# rj45External.net
KiCad netlist of a schematic drawn in EAGLE
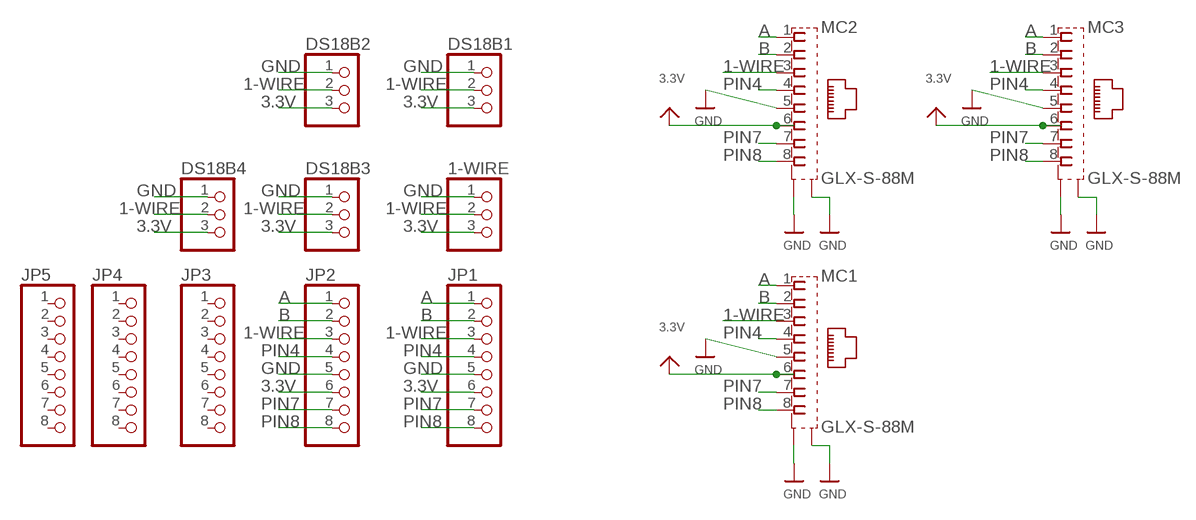
[diagram p0: schematic, sheet 1]

(export (version "E")
  (design (tool "Eeschema 10.0.6"))
  (components
    (comp (ref "1-WIRE")
      (value "PINHD-1X3")
      (footprint "eagle-import:1X03")
      (libsource (lib "eagle-import") (part "PINHD-1X3"))
    )
    (comp (ref "DS18B1")
      (value "PINHD-1X3")
      (footprint "eagle-import:1X03")
      (libsource (lib "eagle-import") (part "PINHD-1X3"))
    )
    (comp (ref "DS18B2")
      (value "PINHD-1X3")
      (footprint "eagle-import:1X03")
      (libsource (lib "eagle-import") (part "PINHD-1X3"))
    )
    (comp (ref "DS18B3")
      (value "PINHD-1X3")
      (footprint "eagle-import:1X03")
      (libsource (lib "eagle-import") (part "PINHD-1X3"))
    )
    (comp (ref "DS18B4")
      (value "PINHD-1X3")
      (footprint "eagle-import:1X03")
      (libsource (lib "eagle-import") (part "PINHD-1X3"))
    )
    (comp (ref "JP1")
      (value "PINHD-1X8BIG")
      (footprint "eagle-import:1X08-BIG")
      (libsource (lib "eagle-import") (part "PINHD-1X8BIG"))
    )
    (comp (ref "JP2")
      (value "PINHD-1X8BIG")
      (footprint "eagle-import:1X08-BIG")
      (libsource (lib "eagle-import") (part "PINHD-1X8BIG"))
    )
    (comp (ref "JP3")
      (value "PINHD-1X8BIG")
      (footprint "eagle-import:1X08-BIG")
      (libsource (lib "eagle-import") (part "PINHD-1X8BIG"))
    )
    (comp (ref "JP4")
      (value "PINHD-1X8BIG")
      (footprint "eagle-import:1X08-BIG")
      (libsource (lib "eagle-import") (part "PINHD-1X8BIG"))
    )
    (comp (ref "JP5")
      (value "PINHD-1X8BIG")
      (footprint "eagle-import:1X08-BIG")
      (libsource (lib "eagle-import") (part "PINHD-1X8BIG"))
    )
    (comp (ref "MC1")
      (value "GLX-S-88M")
      (footprint "eagle-import:GLX-S-88M")
      (libsource (lib "eagle-import") (part "GLX-S-88M"))
    )
    (comp (ref "MC2")
      (value "GLX-S-88M")
      (footprint "eagle-import:GLX-S-88M")
      (libsource (lib "eagle-import") (part "GLX-S-88M"))
    )
    (comp (ref "MC3")
      (value "GLX-S-88M")
      (footprint "eagle-import:GLX-S-88M")
      (libsource (lib "eagle-import") (part "GLX-S-88M"))
    )
  )
  (nets
    (net (code "1") (name "/1-WIRE") (class "Default")
      (node (ref "1-WIRE") (pin "2") (pinfunction "2_2") (pintype "passive"))
      (node (ref "DS18B1") (pin "2") (pinfunction "2_2") (pintype "passive"))
      (node (ref "DS18B2") (pin "2") (pinfunction "2_2") (pintype "passive"))
      (node (ref "DS18B3") (pin "2") (pinfunction "2_2") (pintype "passive"))
      (node (ref "DS18B4") (pin "2") (pinfunction "2_2") (pintype "passive"))
      (node (ref "JP1") (pin "3") (pinfunction "3_3") (pintype "passive"))
      (node (ref "JP2") (pin "3") (pinfunction "3_3") (pintype "passive"))
      (node (ref "MC1") (pin "3") (pinfunction "3_3") (pintype "passive"))
      (node (ref "MC2") (pin "3") (pinfunction "3_3") (pintype "passive"))
      (node (ref "MC3") (pin "3") (pinfunction "3_3") (pintype "passive"))
    )
    (net (code "2") (name "/A") (class "Default")
      (node (ref "JP1") (pin "1") (pinfunction "1_1") (pintype "passive"))
      (node (ref "JP2") (pin "1") (pinfunction "1_1") (pintype "passive"))
      (node (ref "MC1") (pin "1") (pinfunction "1_1") (pintype "passive"))
      (node (ref "MC2") (pin "1") (pinfunction "1_1") (pintype "passive"))
      (node (ref "MC3") (pin "1") (pinfunction "1_1") (pintype "passive"))
    )
    (net (code "3") (name "/B") (class "Default")
      (node (ref "JP1") (pin "2") (pinfunction "2_2") (pintype "passive"))
      (node (ref "JP2") (pin "2") (pinfunction "2_2") (pintype "passive"))
      (node (ref "MC1") (pin "2") (pinfunction "2_2") (pintype "passive"))
      (node (ref "MC2") (pin "2") (pinfunction "2_2") (pintype "passive"))
      (node (ref "MC3") (pin "2") (pinfunction "2_2") (pintype "passive"))
    )
    (net (code "4") (name "/PIN4") (class "Default")
      (node (ref "JP1") (pin "4") (pinfunction "4_4") (pintype "passive"))
      (node (ref "JP2") (pin "4") (pinfunction "4_4") (pintype "passive"))
      (node (ref "MC1") (pin "4") (pinfunction "4_4") (pintype "passive"))
      (node (ref "MC2") (pin "4") (pinfunction "4_4") (pintype "passive"))
      (node (ref "MC3") (pin "4") (pinfunction "4_4") (pintype "passive"))
    )
    (net (code "5") (name "/PIN7") (class "Default")
      (node (ref "JP1") (pin "7") (pinfunction "7_7") (pintype "passive"))
      (node (ref "JP2") (pin "7") (pinfunction "7_7") (pintype "passive"))
      (node (ref "MC1") (pin "7") (pinfunction "7_7") (pintype "passive"))
      (node (ref "MC2") (pin "7") (pinfunction "7_7") (pintype "passive"))
      (node (ref "MC3") (pin "7") (pinfunction "7_7") (pintype "passive"))
    )
    (net (code "6") (name "/PIN8") (class "Default")
      (node (ref "JP1") (pin "8") (pinfunction "8_8") (pintype "passive"))
      (node (ref "JP2") (pin "8") (pinfunction "8_8") (pintype "passive"))
      (node (ref "MC1") (pin "8") (pinfunction "8_8") (pintype "passive"))
      (node (ref "MC2") (pin "8") (pinfunction "8_8") (pintype "passive"))
      (node (ref "MC3") (pin "8") (pinfunction "8_8") (pintype "passive"))
    )
    (net (code "7") (name "3.3V") (class "Default")
      (node (ref "1-WIRE") (pin "3") (pinfunction "3_3") (pintype "passive"))
      (node (ref "DS18B1") (pin "3") (pinfunction "3_3") (pintype "passive"))
      (node (ref "DS18B2") (pin "3") (pinfunction "3_3") (pintype "passive"))
      (node (ref "DS18B3") (pin "3") (pinfunction "3_3") (pintype "passive"))
      (node (ref "DS18B4") (pin "3") (pinfunction "3_3") (pintype "passive"))
      (node (ref "JP1") (pin "6") (pinfunction "6_6") (pintype "passive"))
      (node (ref "JP2") (pin "6") (pinfunction "6_6") (pintype "passive"))
      (node (ref "MC1") (pin "6") (pinfunction "6_6") (pintype "passive"))
      (node (ref "MC2") (pin "6") (pinfunction "6_6") (pintype "passive"))
      (node (ref "MC3") (pin "6") (pinfunction "6_6") (pintype "passive"))
    )
    (net (code "8") (name "GND") (class "Default")
      (node (ref "1-WIRE") (pin "1") (pinfunction "1_1") (pintype "passive"))
      (node (ref "DS18B1") (pin "1") (pinfunction "1_1") (pintype "passive"))
      (node (ref "DS18B2") (pin "1") (pinfunction "1_1") (pintype "passive"))
      (node (ref "DS18B3") (pin "1") (pinfunction "1_1") (pintype "passive"))
      (node (ref "DS18B4") (pin "1") (pinfunction "1_1") (pintype "passive"))
      (node (ref "JP1") (pin "5") (pinfunction "5_5") (pintype "passive"))
      (node (ref "JP2") (pin "5") (pinfunction "5_5") (pintype "passive"))
      (node (ref "MC1") (pin "5") (pinfunction "5_5") (pintype "passive"))
      (node (ref "MC1") (pin "S1") (pinfunction "S1_S1") (pintype "passive"))
      (node (ref "MC1") (pin "S2") (pinfunction "S2_S2") (pintype "passive"))
      (node (ref "MC2") (pin "5") (pinfunction "5_5") (pintype "passive"))
      (node (ref "MC2") (pin "S1") (pinfunction "S1_S1") (pintype "passive"))
      (node (ref "MC2") (pin "S2") (pinfunction "S2_S2") (pintype "passive"))
      (node (ref "MC3") (pin "5") (pinfunction "5_5") (pintype "passive"))
      (node (ref "MC3") (pin "S1") (pinfunction "S1_S1") (pintype "passive"))
      (node (ref "MC3") (pin "S2") (pinfunction "S2_S2") (pintype "passive"))
    )
    (net (code "9") (name "unconnected-(JP3-Pad1)") (class "Default")
      (node (ref "JP3") (pin "1") (pinfunction "1_1") (pintype "passive"))
    )
    (net (code "10") (name "unconnected-(JP3-Pad2)") (class "Default")
      (node (ref "JP3") (pin "2") (pinfunction "2_2") (pintype "passive"))
    )
    (net (code "11") (name "unconnected-(JP3-Pad3)") (class "Default")
      (node (ref "JP3") (pin "3") (pinfunction "3_3") (pintype "passive"))
    )
    (net (code "12") (name "unconnected-(JP3-Pad4)") (class "Default")
      (node (ref "JP3") (pin "4") (pinfunction "4_4") (pintype "passive"))
    )
    (net (code "13") (name "unconnected-(JP3-Pad5)") (class "Default")
      (node (ref "JP3") (pin "5") (pinfunction "5_5") (pintype "passive"))
    )
    (net (code "14") (name "unconnected-(JP3-Pad6)") (class "Default")
      (node (ref "JP3") (pin "6") (pinfunction "6_6") (pintype "passive"))
    )
    (net (code "15") (name "unconnected-(JP3-Pad7)") (class "Default")
      (node (ref "JP3") (pin "7") (pinfunction "7_7") (pintype "passive"))
    )
    (net (code "16") (name "unconnected-(JP3-Pad8)") (class "Default")
      (node (ref "JP3") (pin "8") (pinfunction "8_8") (pintype "passive"))
    )
    (net (code "17") (name "unconnected-(JP4-Pad1)") (class "Default")
      (node (ref "JP4") (pin "1") (pinfunction "1_1") (pintype "passive"))
    )
    (net (code "18") (name "unconnected-(JP4-Pad2)") (class "Default")
      (node (ref "JP4") (pin "2") (pinfunction "2_2") (pintype "passive"))
    )
    (net (code "19") (name "unconnected-(JP4-Pad3)") (class "Default")
      (node (ref "JP4") (pin "3") (pinfunction "3_3") (pintype "passive"))
    )
    (net (code "20") (name "unconnected-(JP4-Pad4)") (class "Default")
      (node (ref "JP4") (pin "4") (pinfunction "4_4") (pintype "passive"))
    )
    (net (code "21") (name "unconnected-(JP4-Pad5)") (class "Default")
      (node (ref "JP4") (pin "5") (pinfunction "5_5") (pintype "passive"))
    )
    (net (code "22") (name "unconnected-(JP4-Pad6)") (class "Default")
      (node (ref "JP4") (pin "6") (pinfunction "6_6") (pintype "passive"))
    )
    (net (code "23") (name "unconnected-(JP4-Pad7)") (class "Default")
      (node (ref "JP4") (pin "7") (pinfunction "7_7") (pintype "passive"))
    )
    (net (code "24") (name "unconnected-(JP4-Pad8)") (class "Default")
      (node (ref "JP4") (pin "8") (pinfunction "8_8") (pintype "passive"))
    )
    (net (code "25") (name "unconnected-(JP5-Pad1)") (class "Default")
      (node (ref "JP5") (pin "1") (pinfunction "1_1") (pintype "passive"))
    )
    (net (code "26") (name "unconnected-(JP5-Pad2)") (class "Default")
      (node (ref "JP5") (pin "2") (pinfunction "2_2") (pintype "passive"))
    )
    (net (code "27") (name "unconnected-(JP5-Pad3)") (class "Default")
      (node (ref "JP5") (pin "3") (pinfunction "3_3") (pintype "passive"))
    )
    (net (code "28") (name "unconnected-(JP5-Pad4)") (class "Default")
      (node (ref "JP5") (pin "4") (pinfunction "4_4") (pintype "passive"))
    )
    (net (code "29") (name "unconnected-(JP5-Pad5)") (class "Default")
      (node (ref "JP5") (pin "5") (pinfunction "5_5") (pintype "passive"))
    )
    (net (code "30") (name "unconnected-(JP5-Pad6)") (class "Default")
      (node (ref "JP5") (pin "6") (pinfunction "6_6") (pintype "passive"))
    )
    (net (code "31") (name "unconnected-(JP5-Pad7)") (class "Default")
      (node (ref "JP5") (pin "7") (pinfunction "7_7") (pintype "passive"))
    )
    (net (code "32") (name "unconnected-(JP5-Pad8)") (class "Default")
      (node (ref "JP5") (pin "8") (pinfunction "8_8") (pintype "passive"))
    )
  )
)
